# BOOSTCONVERTER20K20.net
KiCad netlist of a schematic drawn in EAGLE
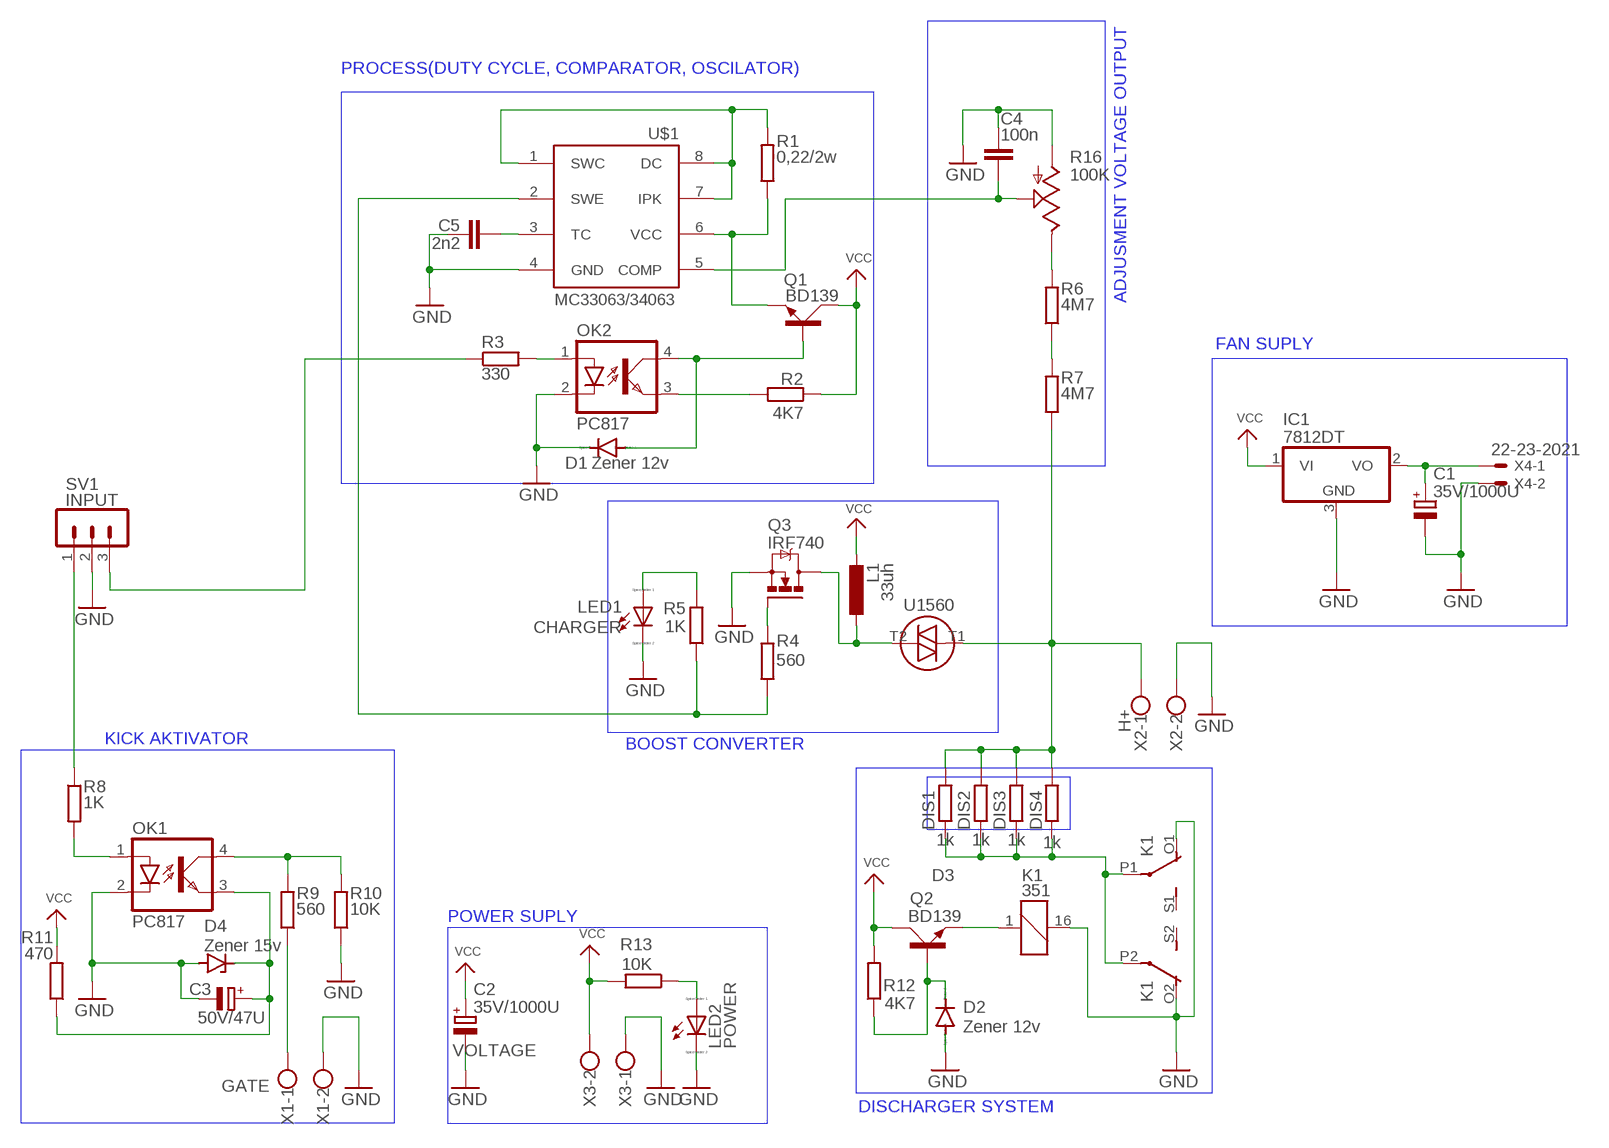
[diagram p0: schematic, sheet 1]

(export (version "E")
  (design (tool "Eeschema 10.0.6"))
  (components
    (comp (ref "C1")
      (value "35V/1000U")
      (footprint "eagle-import:E2,5-7")
      (libsource (lib "eagle-import") (part "CPOL-EUE2.5-7"))
    )
    (comp (ref "C2")
      (value "35V/1000U")
      (footprint "eagle-import:E2,5-7")
      (libsource (lib "eagle-import") (part "CPOL-EUE2.5-7"))
    )
    (comp (ref "C3")
      (value "50V/47U")
      (footprint "eagle-import:153CLV-0810")
      (libsource (lib "eagle-import") (part "CPOL-EU153CLV-0810"))
    )
    (comp (ref "C4")
      (value "100n")
      (footprint "eagle-import:C0805K")
      (libsource (lib "eagle-import") (part "C-EUC0805K"))
    )
    (comp (ref "C5")
      (value "2n2")
      (footprint "eagle-import:C0805K")
      (libsource (lib "eagle-import") (part "C-EUC0805K"))
    )
    (comp (ref "D1")
      (value "Zener 12v")
      (footprint "eagle-import:DO35-7")
      (libsource (lib "eagle-import") (part "1N4148DO35-7"))
    )
    (comp (ref "D2")
      (value "Zener 12v")
      (footprint "eagle-import:DO35-7")
      (libsource (lib "eagle-import") (part "1N4148DO35-7"))
    )
    (comp (ref "D3")
      (value "U1560")
      (footprint "eagle-import:BR210S")
      (libsource (lib "eagle-import") (part "BR210"))
    )
    (comp (ref "D4")
      (value "Zener 15v")
      (footprint "eagle-import:DO35Z10")
      (libsource (lib "eagle-import") (part "BZX55"))
    )
    (comp (ref "DIS1")
      (value "1k")
      (footprint "eagle-import:VTA53")
      (libsource (lib "eagle-import") (part "R-EU_VTA53"))
    )
    (comp (ref "DIS2")
      (value "1k")
      (footprint "eagle-import:VTA53")
      (libsource (lib "eagle-import") (part "R-EU_VTA53"))
    )
    (comp (ref "DIS3")
      (value "1k")
      (footprint "eagle-import:VTA53")
      (libsource (lib "eagle-import") (part "R-EU_VTA53"))
    )
    (comp (ref "DIS4")
      (value "1k")
      (footprint "eagle-import:VTA53")
      (libsource (lib "eagle-import") (part "R-EU_VTA53"))
    )
    (comp (ref "IC1")
      (value "7812DT")
      (footprint "eagle-import:TO252")
      (libsource (lib "eagle-import") (part "78DT12"))
    )
    (comp (ref "K1")
      (value "351")
      (footprint "eagle-import:351")
      (libsource (lib "eagle-import") (part "351"))
    )
    (comp (ref "L1")
      (value "33uh")
      (footprint "eagle-import:TJ3-U2")
      (libsource (lib "eagle-import") (part "L-EUTJ3-U2"))
    )
    (comp (ref "LED1")
      (value "CHARGER")
      (footprint "eagle-import:LED_1206")
      (libsource (lib "eagle-import") (part "LED_E"))
    )
    (comp (ref "LED2")
      (value "POWER")
      (footprint "eagle-import:LED_1206")
      (libsource (lib "eagle-import") (part "LED_E"))
    )
    (comp (ref "OK1")
      (value "PC817")
      (footprint "eagle-import:DIL04")
      (fields (field (name "MPN") "PC817X4J000F"))
      (libsource (lib "eagle-import") (part "PC817"))
    )
    (comp (ref "OK2")
      (value "PC817")
      (footprint "eagle-import:DIL04")
      (fields (field (name "MPN") "PC817X4J000F"))
      (libsource (lib "eagle-import") (part "PC817"))
    )
    (comp (ref "Q1")
      (value "BD139")
      (footprint "eagle-import:TO126AV")
      (libsource (lib "eagle-import") (part "BD139"))
    )
    (comp (ref "Q2")
      (value "BD139")
      (footprint "eagle-import:TO126AV")
      (libsource (lib "eagle-import") (part "BD139"))
    )
    (comp (ref "Q3")
      (value "IRF740")
      (footprint "eagle-import:TO220BV")
      (libsource (lib "eagle-import") (part "IRF740"))
    )
    (comp (ref "R1")
      (value "0,22/2w")
      (footprint "eagle-import:M1206")
      (libsource (lib "eagle-import") (part "R-EU_M1206"))
    )
    (comp (ref "R2")
      (value "4K7")
      (footprint "eagle-import:M1206")
      (libsource (lib "eagle-import") (part "R-EU_M1206"))
    )
    (comp (ref "R3")
      (value "330")
      (footprint "eagle-import:M1206")
      (libsource (lib "eagle-import") (part "R-EU_M1206"))
    )
    (comp (ref "R4")
      (value "560")
      (footprint "eagle-import:M1206")
      (libsource (lib "eagle-import") (part "R-EU_M1206"))
    )
    (comp (ref "R5")
      (value "1K")
      (footprint "eagle-import:M1206")
      (libsource (lib "eagle-import") (part "R-EU_M1206"))
    )
    (comp (ref "R6")
      (value "4M7")
      (footprint "eagle-import:0309_10")
      (libsource (lib "eagle-import") (part "R-EU_0309/10"))
    )
    (comp (ref "R7")
      (value "4M7")
      (footprint "eagle-import:0309_10")
      (libsource (lib "eagle-import") (part "R-EU_0309/10"))
    )
    (comp (ref "R8")
      (value "1K")
      (footprint "eagle-import:M1206")
      (libsource (lib "eagle-import") (part "R-EU_M1206"))
    )
    (comp (ref "R9")
      (value "560")
      (footprint "eagle-import:M1206")
      (libsource (lib "eagle-import") (part "R-EU_M1206"))
    )
    (comp (ref "R10")
      (value "10K")
      (footprint "eagle-import:M1206")
      (libsource (lib "eagle-import") (part "R-EU_M1206"))
    )
    (comp (ref "R11")
      (value "470")
      (footprint "eagle-import:M1206")
      (libsource (lib "eagle-import") (part "R-EU_M1206"))
    )
    (comp (ref "R12")
      (value "4K7")
      (footprint "eagle-import:M1206")
      (libsource (lib "eagle-import") (part "R-EU_M1206"))
    )
    (comp (ref "R13")
      (value "10K")
      (footprint "eagle-import:M1206")
      (libsource (lib "eagle-import") (part "R-EU_M1206"))
    )
    (comp (ref "R16")
      (value "100K")
      (footprint "eagle-import:CA6V")
      (libsource (lib "eagle-import") (part "TRIM_US-CA6V"))
    )
    (comp (ref "SV1")
      (value "INPUT")
      (footprint "eagle-import:MA03-1")
      (libsource (lib "eagle-import") (part "MA03-1"))
    )
    (comp (ref "U$1")
      (value "MC33063/MC34063D")
      (footprint "eagle-import:SO08")
      (libsource (lib "eagle-import") (part "MC33063/MC34063D"))
    )
    (comp (ref "X1")
      (value "GATE")
      (footprint "eagle-import:W237-102")
      (fields (field (name "MPN") "237-102"))
      (libsource (lib "eagle-import") (part "W237-102"))
    )
    (comp (ref "X2")
      (value "H+")
      (footprint "eagle-import:W237-102")
      (fields (field (name "MPN") "237-102"))
      (libsource (lib "eagle-import") (part "W237-102"))
    )
    (comp (ref "X3")
      (value "VOLTAGE")
      (footprint "eagle-import:W237-102")
      (fields (field (name "MPN") "237-102"))
      (libsource (lib "eagle-import") (part "W237-102"))
    )
    (comp (ref "X4")
      (value "22-23-2021")
      (footprint "eagle-import:22-23-2021")
      (fields (field (name "MF") "MOLEX"))
      (libsource (lib "eagle-import") (part "22-23-2021"))
    )
  )
  (nets
    (net (code "1") (name "GND") (class "Default")
      (node (ref "C1") (pin "-") (pinfunction "-_-") (pintype "passive"))
      (node (ref "C2") (pin "-") (pinfunction "-_-") (pintype "passive"))
      (node (ref "C3") (pin "-") (pinfunction "-_-") (pintype "passive"))
      (node (ref "C4") (pin "1") (pinfunction "1_1") (pintype "passive"))
      (node (ref "C5") (pin "1") (pinfunction "1_1") (pintype "passive"))
      (node (ref "D1") (pin "C") (pinfunction "C_C") (pintype "passive"))
      (node (ref "D2") (pin "A") (pinfunction "A_A") (pintype "passive"))
      (node (ref "D4") (pin "A") (pinfunction "A_A") (pintype "passive"))
      (node (ref "IC1") (pin "3") (pinfunction "GND_3") (pintype "passive"))
      (node (ref "K1") (pin "16") (pinfunction "2_16") (pintype "passive"))
      (node (ref "K1") (pin "O1") (pinfunction "O_O1") (pintype "passive"))
      (node (ref "K1") (pin "O2") (pinfunction "O_O2") (pintype "passive"))
      (node (ref "LED1") (pin "C") (pinfunction "C_C") (pintype "passive"))
      (node (ref "LED2") (pin "C") (pinfunction "C_C") (pintype "passive"))
      (node (ref "OK1") (pin "2") (pinfunction "C_2") (pintype "passive"))
      (node (ref "OK2") (pin "2") (pinfunction "C_2") (pintype "passive"))
      (node (ref "Q3") (pin "S") (pinfunction "S_S") (pintype "passive"))
      (node (ref "R10") (pin "1") (pinfunction "1_1") (pintype "passive"))
      (node (ref "R16") (pin "A") (pinfunction "A_A") (pintype "passive"))
      (node (ref "SV1") (pin "2") (pinfunction "2_2") (pintype "passive"))
      (node (ref "U$1") (pin "4") (pinfunction "GND_4") (pintype "power_in"))
      (node (ref "X1") (pin "2") (pinfunction "KL_2") (pintype "passive"))
      (node (ref "X2") (pin "2") (pinfunction "KL_2") (pintype "passive"))
      (node (ref "X3") (pin "1") (pinfunction "KL_1") (pintype "passive"))
      (node (ref "X4") (pin "2") (pinfunction "S_2") (pintype "passive"))
    )
    (net (code "2") (name "Net-(D2-PadC)") (class "Default")
      (node (ref "D2") (pin "C") (pinfunction "C_C") (pintype "passive"))
      (node (ref "Q2") (pin "B") (pinfunction "B_B") (pintype "passive"))
      (node (ref "R12") (pin "1") (pinfunction "1_1") (pintype "passive"))
    )
    (net (code "3") (name "Net-(D3-PadT2)") (class "Default")
      (node (ref "D3") (pin "T2") (pinfunction "T2_T2") (pintype "passive"))
      (node (ref "L1") (pin "1") (pinfunction "1_1") (pintype "passive"))
      (node (ref "Q3") (pin "D") (pinfunction "D_D") (pintype "passive"))
    )
    (net (code "4") (name "Net-(IC1-VO)") (class "Default")
      (node (ref "C1") (pin "+") (pinfunction "+_+") (pintype "passive"))
      (node (ref "IC1") (pin "2") (pinfunction "VO_2") (pintype "passive"))
      (node (ref "X4") (pin "1") (pinfunction "S_1") (pintype "passive"))
    )
    (net (code "5") (name "Net-(K1-Pad1)") (class "Default")
      (node (ref "K1") (pin "1") (pinfunction "1_1") (pintype "passive"))
      (node (ref "Q2") (pin "E") (pinfunction "E_E") (pintype "passive"))
    )
    (net (code "6") (name "Net-(K1B-P)") (class "Default")
      (node (ref "DIS1") (pin "1") (pinfunction "1_1") (pintype "passive"))
      (node (ref "DIS2") (pin "1") (pinfunction "1_1") (pintype "passive"))
      (node (ref "DIS3") (pin "1") (pinfunction "1_1") (pintype "passive"))
      (node (ref "DIS4") (pin "1") (pinfunction "1_1") (pintype "passive"))
      (node (ref "K1") (pin "P1") (pinfunction "P_P1") (pintype "passive"))
      (node (ref "K1") (pin "P2") (pinfunction "P_P2") (pintype "passive"))
    )
    (net (code "7") (name "Net-(LED1-PadA)") (class "Default")
      (node (ref "LED1") (pin "A") (pinfunction "A_A") (pintype "passive"))
      (node (ref "R5") (pin "2") (pinfunction "2_2") (pintype "passive"))
    )
    (net (code "8") (name "Net-(LED2-PadA)") (class "Default")
      (node (ref "LED2") (pin "A") (pinfunction "A_A") (pintype "passive"))
      (node (ref "R13") (pin "1") (pinfunction "1_1") (pintype "passive"))
    )
    (net (code "9") (name "Net-(OK1-A)") (class "Default")
      (node (ref "OK1") (pin "1") (pinfunction "A_1") (pintype "passive"))
      (node (ref "R8") (pin "2") (pinfunction "2_2") (pintype "passive"))
    )
    (net (code "10") (name "Net-(OK1-COL)") (class "Default")
      (node (ref "OK1") (pin "4") (pinfunction "COL_4") (pintype "passive"))
      (node (ref "R10") (pin "2") (pinfunction "2_2") (pintype "passive"))
      (node (ref "R9") (pin "2") (pinfunction "2_2") (pintype "passive"))
    )
    (net (code "11") (name "Net-(OK1-EMIT)") (class "Default")
      (node (ref "C3") (pin "+") (pinfunction "+_+") (pintype "passive"))
      (node (ref "D4") (pin "C") (pinfunction "C_C") (pintype "passive"))
      (node (ref "OK1") (pin "3") (pinfunction "EMIT_3") (pintype "passive"))
      (node (ref "R11") (pin "1") (pinfunction "1_1") (pintype "passive"))
    )
    (net (code "12") (name "Net-(OK2-A)") (class "Default")
      (node (ref "OK2") (pin "1") (pinfunction "A_1") (pintype "passive"))
      (node (ref "R3") (pin "2") (pinfunction "2_2") (pintype "passive"))
    )
    (net (code "13") (name "Net-(OK2-COL)") (class "Default")
      (node (ref "D1") (pin "A") (pinfunction "A_A") (pintype "passive"))
      (node (ref "OK2") (pin "4") (pinfunction "COL_4") (pintype "passive"))
      (node (ref "Q1") (pin "B") (pinfunction "B_B") (pintype "passive"))
    )
    (net (code "14") (name "Net-(OK2-EMIT)") (class "Default")
      (node (ref "OK2") (pin "3") (pinfunction "EMIT_3") (pintype "passive"))
      (node (ref "R2") (pin "2") (pinfunction "2_2") (pintype "passive"))
    )
    (net (code "15") (name "Net-(Q3-PadG)") (class "Default")
      (node (ref "Q3") (pin "G") (pinfunction "G_G") (pintype "passive"))
      (node (ref "R4") (pin "1") (pinfunction "1_1") (pintype "passive"))
    )
    (net (code "16") (name "Net-(R3-Pad1)") (class "Default")
      (node (ref "R3") (pin "1") (pinfunction "1_1") (pintype "passive"))
      (node (ref "SV1") (pin "3") (pinfunction "3_3") (pintype "passive"))
    )
    (net (code "17") (name "Net-(R6-Pad1)") (class "Default")
      (node (ref "R6") (pin "1") (pinfunction "1_1") (pintype "passive"))
      (node (ref "R7") (pin "2") (pinfunction "2_2") (pintype "passive"))
    )
    (net (code "18") (name "Net-(R8-Pad1)") (class "Default")
      (node (ref "R8") (pin "1") (pinfunction "1_1") (pintype "passive"))
      (node (ref "SV1") (pin "1") (pinfunction "1_1") (pintype "passive"))
    )
    (net (code "19") (name "Net-(R16-PadE)") (class "Default")
      (node (ref "R16") (pin "E") (pinfunction "E_E") (pintype "passive"))
      (node (ref "R6") (pin "2") (pinfunction "2_2") (pintype "passive"))
    )
    (net (code "20") (name "Net-(U$1-COMP)") (class "Default")
      (node (ref "C4") (pin "2") (pinfunction "2_2") (pintype "passive"))
      (node (ref "R16") (pin "S") (pinfunction "S_S") (pintype "passive"))
      (node (ref "U$1") (pin "5") (pinfunction "COMP_5") (pintype "input"))
    )
    (net (code "21") (name "Net-(U$1-DC)") (class "Default")
      (node (ref "R1") (pin "2") (pinfunction "2_2") (pintype "passive"))
      (node (ref "U$1") (pin "1") (pinfunction "SWC_1") (pintype "input"))
      (node (ref "U$1") (pin "7") (pinfunction "IPK_7") (pintype "bidirectional"))
      (node (ref "U$1") (pin "8") (pinfunction "DC_8") (pintype "input"))
    )
    (net (code "22") (name "Net-(U$1-SWE)") (class "Default")
      (node (ref "R4") (pin "2") (pinfunction "2_2") (pintype "passive"))
      (node (ref "R5") (pin "1") (pinfunction "1_1") (pintype "passive"))
      (node (ref "U$1") (pin "2") (pinfunction "SWE_2") (pintype "input"))
    )
    (net (code "23") (name "Net-(U$1-TC)") (class "Default")
      (node (ref "C5") (pin "2") (pinfunction "2_2") (pintype "passive"))
      (node (ref "U$1") (pin "3") (pinfunction "TC_3") (pintype "input"))
    )
    (net (code "24") (name "Net-(U$1-VCC)") (class "Default")
      (node (ref "Q1") (pin "E") (pinfunction "E_E") (pintype "passive"))
      (node (ref "R1") (pin "1") (pinfunction "1_1") (pintype "passive"))
      (node (ref "U$1") (pin "6") (pinfunction "VCC_6") (pintype "power_in"))
    )
    (net (code "25") (name "Net-(X1A-KL)") (class "Default")
      (node (ref "R9") (pin "1") (pinfunction "1_1") (pintype "passive"))
      (node (ref "X1") (pin "1") (pinfunction "KL_1") (pintype "passive"))
    )
    (net (code "26") (name "Net-(X2A-KL)") (class "Default")
      (node (ref "D3") (pin "T1") (pinfunction "T1_T1") (pintype "passive"))
      (node (ref "DIS1") (pin "2") (pinfunction "2_2") (pintype "passive"))
      (node (ref "DIS2") (pin "2") (pinfunction "2_2") (pintype "passive"))
      (node (ref "DIS3") (pin "2") (pinfunction "2_2") (pintype "passive"))
      (node (ref "DIS4") (pin "2") (pinfunction "2_2") (pintype "passive"))
      (node (ref "R7") (pin "1") (pinfunction "1_1") (pintype "passive"))
      (node (ref "X2") (pin "1") (pinfunction "KL_1") (pintype "passive"))
    )
    (net (code "27") (name "VCC") (class "Default")
      (node (ref "C2") (pin "+") (pinfunction "+_+") (pintype "passive"))
      (node (ref "IC1") (pin "1") (pinfunction "VI_1") (pintype "input"))
      (node (ref "L1") (pin "2") (pinfunction "2_2") (pintype "passive"))
      (node (ref "Q1") (pin "C") (pinfunction "C_C") (pintype "passive"))
      (node (ref "Q2") (pin "C") (pinfunction "C_C") (pintype "passive"))
      (node (ref "R11") (pin "2") (pinfunction "2_2") (pintype "passive"))
      (node (ref "R12") (pin "2") (pinfunction "2_2") (pintype "passive"))
      (node (ref "R13") (pin "2") (pinfunction "2_2") (pintype "passive"))
      (node (ref "R2") (pin "1") (pinfunction "1_1") (pintype "passive"))
      (node (ref "X3") (pin "2") (pinfunction "KL_2") (pintype "passive"))
    )
    (net (code "28") (name "unconnected-(K1B-S-PadS1)") (class "Default")
      (node (ref "K1") (pin "S1") (pinfunction "S_S1") (pintype "passive"))
    )
    (net (code "29") (name "unconnected-(K1C-S-PadS2)") (class "Default")
      (node (ref "K1") (pin "S2") (pinfunction "S_S2") (pintype "passive"))
    )
  )
)
